# i2c_to_gpio.net
KiCad netlist of a schematic drawn in Altium Designer
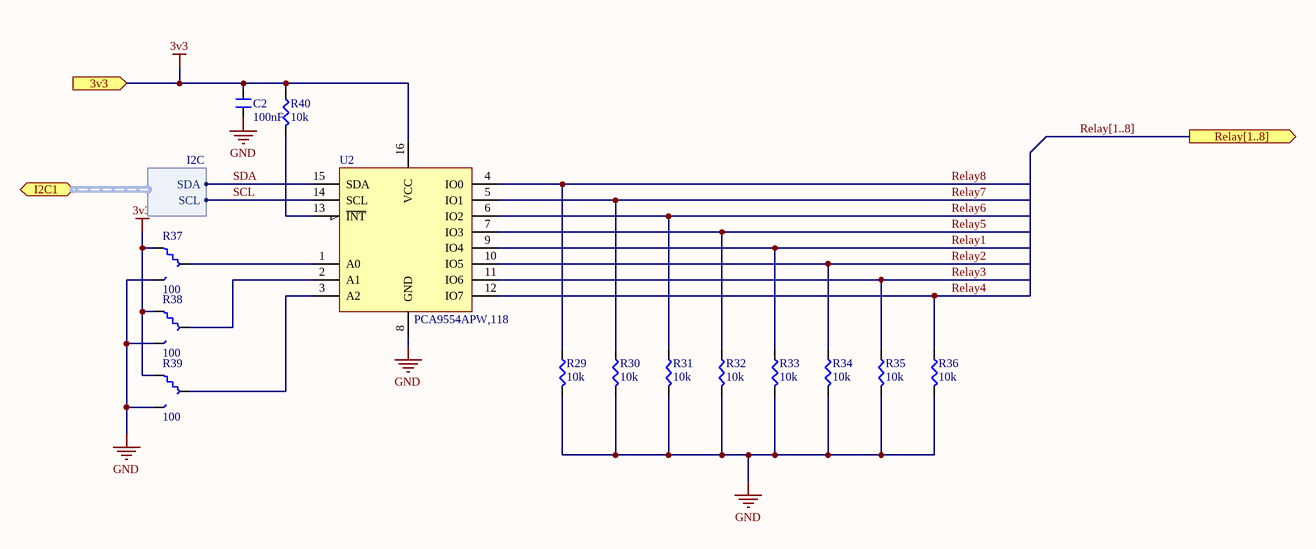
[diagram p0: i2c_to_gpio.SchDoc]

(export (version "E")
  (design (tool "Eeschema 10.0.6"))
  (components
    (comp (ref "C2")
      (value "100nF")
      (footprint "CAP0603")
      (description "Tolerance ±10%\nRated Voltage 50Vdc\nTemperature 0±30ppm/℃")
      (fields (field (name "PART NUMBER") "GCM188R71H104KA57J") (field (name "TOLERANCE") "10%"))
      (libsource (lib "Lib_Kam") (part "Capacitor"))
    )
    (comp (ref "R29")
      (value "10k")
      (footprint "RES0603")
      (description "Tolerance ±1%\nPower (Watts) 0.1W, 1/10W\nTemperature Coefficient ±100ppm/°C")
      (fields (field (name "PART NUMBER") "CR0603-FX-1002ELF") (field (name "TOLERANCE") "1%"))
      (libsource (lib "Lib_Kam") (part "Resistor"))
    )
    (comp (ref "R30")
      (value "10k")
      (footprint "RES0603")
      (description "Tolerance ±1%\nPower (Watts) 0.1W, 1/10W\nTemperature Coefficient ±100ppm/°C")
      (fields (field (name "PART NUMBER") "CR0603-FX-1002ELF") (field (name "TOLERANCE") "1%"))
      (libsource (lib "Lib_Kam") (part "Resistor"))
    )
    (comp (ref "R31")
      (value "10k")
      (footprint "RES0603")
      (description "Tolerance ±1%\nPower (Watts) 0.1W, 1/10W\nTemperature Coefficient ±100ppm/°C")
      (fields (field (name "PART NUMBER") "CR0603-FX-1002ELF") (field (name "TOLERANCE") "1%"))
      (libsource (lib "Lib_Kam") (part "Resistor"))
    )
    (comp (ref "R32")
      (value "10k")
      (footprint "RES0603")
      (description "Tolerance ±1%\nPower (Watts) 0.1W, 1/10W\nTemperature Coefficient ±100ppm/°C")
      (fields (field (name "PART NUMBER") "CR0603-FX-1002ELF") (field (name "TOLERANCE") "1%"))
      (libsource (lib "Lib_Kam") (part "Resistor"))
    )
    (comp (ref "R33")
      (value "10k")
      (footprint "RES0603")
      (description "Tolerance ±1%\nPower (Watts) 0.1W, 1/10W\nTemperature Coefficient ±100ppm/°C")
      (fields (field (name "PART NUMBER") "CR0603-FX-1002ELF") (field (name "TOLERANCE") "1%"))
      (libsource (lib "Lib_Kam") (part "Resistor"))
    )
    (comp (ref "R34")
      (value "10k")
      (footprint "RES0603")
      (description "Tolerance ±1%\nPower (Watts) 0.1W, 1/10W\nTemperature Coefficient ±100ppm/°C")
      (fields (field (name "PART NUMBER") "CR0603-FX-1002ELF") (field (name "TOLERANCE") "1%"))
      (libsource (lib "Lib_Kam") (part "Resistor"))
    )
    (comp (ref "R35")
      (value "10k")
      (footprint "RES0603")
      (description "Tolerance ±1%\nPower (Watts) 0.1W, 1/10W\nTemperature Coefficient ±100ppm/°C")
      (fields (field (name "PART NUMBER") "CR0603-FX-1002ELF") (field (name "TOLERANCE") "1%"))
      (libsource (lib "Lib_Kam") (part "Resistor"))
    )
    (comp (ref "R36")
      (value "10k")
      (footprint "RES0603")
      (description "Tolerance ±1%\nPower (Watts) 0.1W, 1/10W\nTemperature Coefficient ±100ppm/°C")
      (fields (field (name "PART NUMBER") "CR0603-FX-1002ELF") (field (name "TOLERANCE") "1%"))
      (libsource (lib "Lib_Kam") (part "Resistor"))
    )
    (comp (ref "R37")
      (value "100")
      (footprint "RES0603_CHANGE")
      (description "Tolerance ±1%\nPower (Watts) 0.1W, 1/10W\nTemperature Coefficient ±100ppm/°C")
      (fields (field (name "PART NUMBER") "ERJ-3EKF9101V (Jump_RES)") (field (name "TOLERANCE") "1%"))
      (libsource (lib "Lib_Kam") (part "ResistorChange"))
    )
    (comp (ref "R38")
      (value "100")
      (footprint "RES0603_CHANGE")
      (description "Tolerance ±1%\nPower (Watts) 0.1W, 1/10W\nTemperature Coefficient ±100ppm/°C")
      (fields (field (name "PART NUMBER") "ERJ-3EKF9101V (Jump_RES)") (field (name "TOLERANCE") "1%"))
      (libsource (lib "Lib_Kam") (part "ResistorChange"))
    )
    (comp (ref "R39")
      (value "100")
      (footprint "RES0603_CHANGE")
      (description "Tolerance ±1%\nPower (Watts) 0.1W, 1/10W\nTemperature Coefficient ±100ppm/°C")
      (fields (field (name "PART NUMBER") "ERJ-3EKF9101V (Jump_RES)") (field (name "TOLERANCE") "1%"))
      (libsource (lib "Lib_Kam") (part "ResistorChange"))
    )
    (comp (ref "R40")
      (value "10k")
      (footprint "RES0603")
      (description "Tolerance ±1%\nPower (Watts) 0.1W, 1/10W\nTemperature Coefficient ±100ppm/°C")
      (fields (field (name "PART NUMBER") "CR0603-FX-1002ELF") (field (name "TOLERANCE") "1%"))
      (libsource (lib "Lib_Kam") (part "Resistor"))
    )
    (comp (ref "U2")
      (value "PCA9554APW,118")
      (footprint "TSSOP16")
      (description "Interface - I/O Expander I2C I/O")
      (fields (field (name "MANUFACTURER") "NXP"))
      (libsource (lib "Lib_Kam") (part "PCA9554"))
    )
  )
  (nets
    (net (code "2") (name "/Relay1") (class "Default")
      (node (ref "R33") (pin "1") (pintype "passive"))
      (node (ref "U2") (pin "9") (pinfunction "IO4_9") (pintype "passive"))
    )
    (net (code "3") (name "/Relay2") (class "Default")
      (node (ref "R34") (pin "1") (pintype "passive"))
      (node (ref "U2") (pin "10") (pinfunction "IO5_10") (pintype "passive"))
    )
    (net (code "4") (name "/Relay3") (class "Default")
      (node (ref "R35") (pin "1") (pintype "passive"))
      (node (ref "U2") (pin "11") (pinfunction "IO6_11") (pintype "passive"))
    )
    (net (code "5") (name "/Relay4") (class "Default")
      (node (ref "R36") (pin "1") (pintype "passive"))
      (node (ref "U2") (pin "12") (pinfunction "IO7_12") (pintype "passive"))
    )
    (net (code "6") (name "/Relay5") (class "Default")
      (node (ref "R32") (pin "1") (pintype "passive"))
      (node (ref "U2") (pin "7") (pinfunction "IO3_7") (pintype "passive"))
    )
    (net (code "7") (name "/Relay6") (class "Default")
      (node (ref "R31") (pin "1") (pintype "passive"))
      (node (ref "U2") (pin "6") (pinfunction "IO2_6") (pintype "passive"))
    )
    (net (code "8") (name "/Relay7") (class "Default")
      (node (ref "R30") (pin "1") (pintype "passive"))
      (node (ref "U2") (pin "5") (pinfunction "IO1_5") (pintype "passive"))
    )
    (net (code "9") (name "/Relay8") (class "Default")
      (node (ref "R29") (pin "1") (pintype "passive"))
      (node (ref "U2") (pin "4") (pinfunction "IO0_4") (pintype "passive"))
    )
    (net (code "11") (name "/SCL") (class "Default")
      (node (ref "U2") (pin "14") (pinfunction "SCL_14") (pintype "passive"))
    )
    (net (code "12") (name "/SDA") (class "Default")
      (node (ref "U2") (pin "15") (pinfunction "SDA_15") (pintype "passive"))
    )
    (net (code "14") (name "3v3") (class "Default")
      (node (ref "C2") (pin "2") (pinfunction "2_2") (pintype "passive"))
      (node (ref "R37") (pin "1") (pintype "passive"))
      (node (ref "R38") (pin "1") (pintype "passive"))
      (node (ref "R39") (pin "1") (pintype "passive"))
      (node (ref "R40") (pin "1") (pintype "passive"))
      (node (ref "U2") (pin "16") (pinfunction "VCC_16") (pintype "passive"))
    )
    (net (code "15") (name "GND") (class "Default")
      (node (ref "C2") (pin "1") (pinfunction "2_1") (pintype "passive"))
      (node (ref "R29") (pin "2") (pintype "passive"))
      (node (ref "R30") (pin "2") (pintype "passive"))
      (node (ref "R31") (pin "2") (pintype "passive"))
      (node (ref "R32") (pin "2") (pintype "passive"))
      (node (ref "R33") (pin "2") (pintype "passive"))
      (node (ref "R34") (pin "2") (pintype "passive"))
      (node (ref "R35") (pin "2") (pintype "passive"))
      (node (ref "R36") (pin "2") (pintype "passive"))
      (node (ref "R37") (pin "3") (pintype "passive"))
      (node (ref "R38") (pin "3") (pintype "passive"))
      (node (ref "R39") (pin "3") (pintype "passive"))
      (node (ref "U2") (pin "8") (pinfunction "GND_8") (pintype "power_in"))
    )
    (net (code "16") (name "Net-(U2-A0)") (class "Default")
      (node (ref "R37") (pin "2") (pintype "passive"))
      (node (ref "U2") (pin "1") (pinfunction "A0_1") (pintype "passive"))
    )
    (net (code "17") (name "Net-(U2-A1)") (class "Default")
      (node (ref "R38") (pin "2") (pintype "passive"))
      (node (ref "U2") (pin "2") (pinfunction "A1_2") (pintype "passive"))
    )
    (net (code "18") (name "Net-(U2-A2)") (class "Default")
      (node (ref "R39") (pin "2") (pintype "passive"))
      (node (ref "U2") (pin "3") (pinfunction "A2_3") (pintype "passive"))
    )
    (net (code "19") (name "Net-(U2-~{INT})") (class "Default")
      (node (ref "R40") (pin "2") (pintype "passive"))
      (node (ref "U2") (pin "13") (pinfunction "~{INT}_13") (pintype "passive"))
    )
  )
)
